# FE_Channel.net
KiCad netlist of a schematic drawn in Altium Designer
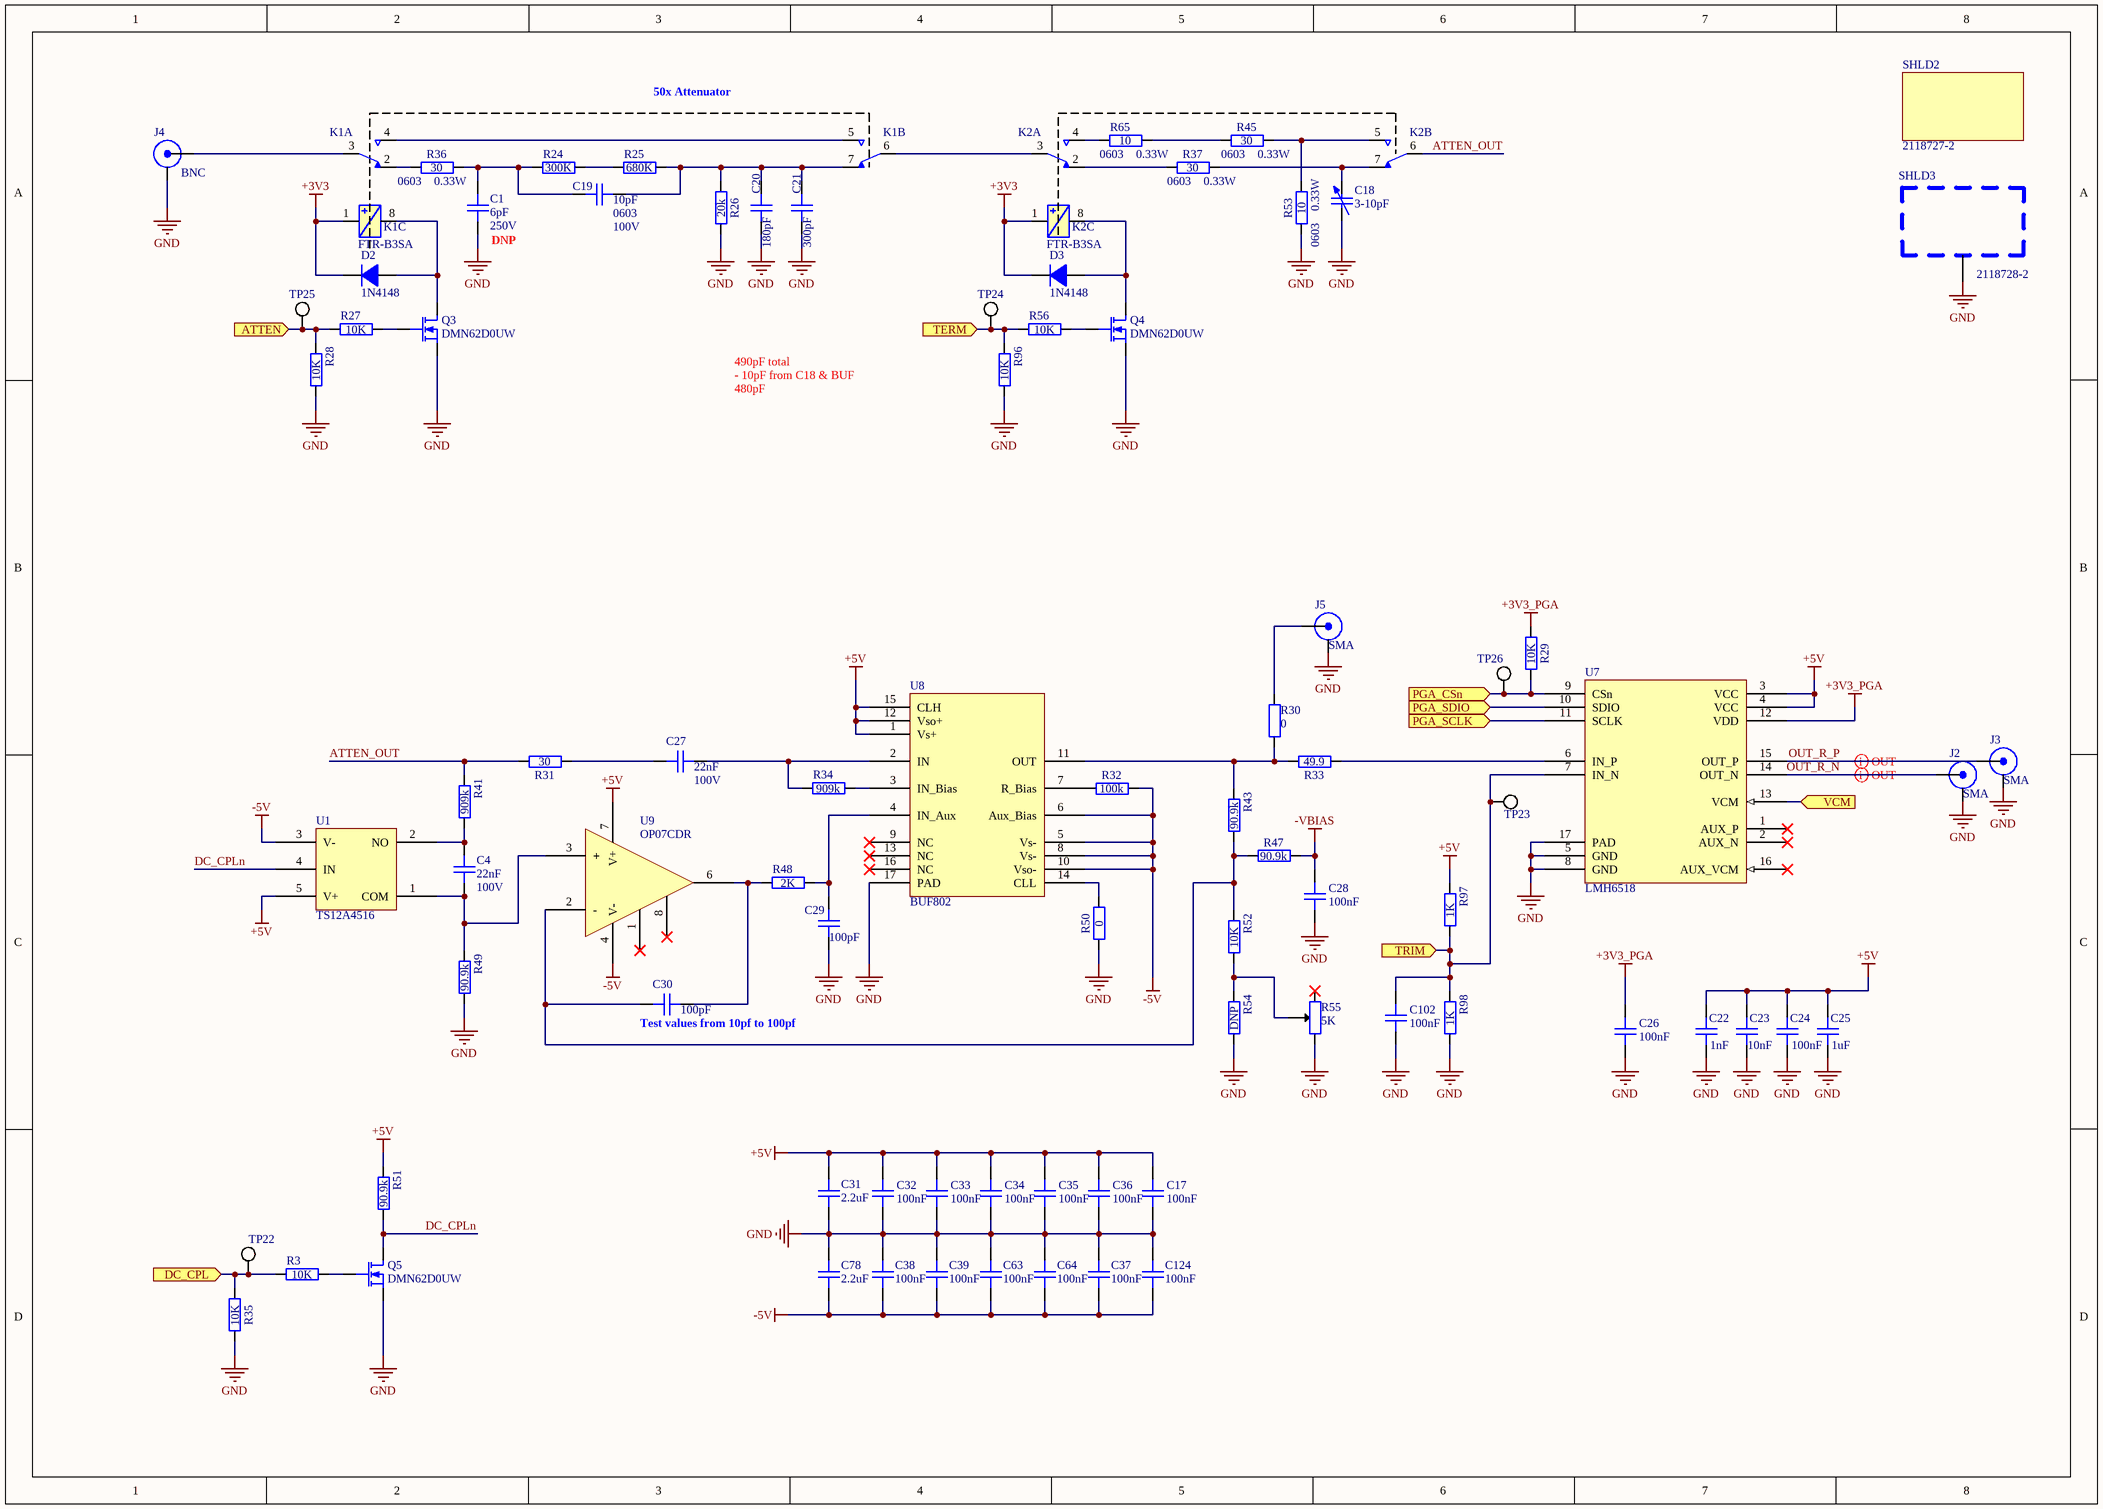
[diagram p0: FE_Channel.SchDoc]

(export (version "E")
  (design (tool "Eeschema 10.0.6"))
  (components
    (comp (ref "C1")
      (value "6pF")
      (footprint "GEN_C_0603")
      (fields
        (field (name "MANUFACTURER") "KEMET")
        (field (name "MANUFACTURER PART NUMBER") "CBR06C609BAGAC")
        (field (name "VOLTAGE RATING") "250V")
      )
      (libsource (lib "DSO") (part "CAP 6pF 250V C0G 0603"))
    )
    (comp (ref "C4")
      (value "22nF")
      (footprint "GEN_C_0603")
      (fields (field (name "VOLTAGE RATING") "100V"))
      (libsource (lib "DSO") (part "CAP 22nF 100V X7R 0603"))
    )
    (comp (ref "C17")
      (value "100nF")
      (footprint "GEN_C_0402")
      (libsource (lib "DSO") (part "CAP 100nF 16V X7R 0402"))
    )
    (comp (ref "C18")
      (value "3-10pF")
      (footprint "EW_TRIMCAP")
      (fields (field (name "MANUFACTURER") "Panasonic") (field (name "MANUFACTURER PART NUMBER") "SGC3S100"))
      (libsource (lib "DSO") (part "CAP TRIMMER 3-10PF 100V SMD"))
    )
    (comp (ref "C19")
      (value "10pF")
      (footprint "GEN_C_0603")
      (fields (field (name "PACKAGE") "0603") (field (name "VOLTAGE RATING") "100V"))
      (libsource (lib "DSO") (part "CAP 10pF 100V C0G 0603"))
    )
    (comp (ref "C20")
      (value "180pF")
      (footprint "GEN_C_0402")
      (fields
        (field (name "MANUFACTURER") "Murata")
        (field (name "MANUFACTURER PART NUMBER") "GCM1555C1H301FA16D")
      )
      (libsource (lib "DSO") (part "CAP 180pF 50V C0G 0402"))
    )
    (comp (ref "C21")
      (value "300pF")
      (footprint "GEN_C_0402")
      (libsource (lib "DSO") (part "CAP 300pF 50V C0G 0402"))
    )
    (comp (ref "C22")
      (value "1nF")
      (footprint "GEN_C_0402")
      (libsource (lib "DSO") (part "CAP 1nF 50V C0G 0402"))
    )
    (comp (ref "C23")
      (value "10nF")
      (footprint "GEN_C_0402")
      (libsource (lib "DSO") (part "CAP 10nF 50V X7R 0402"))
    )
    (comp (ref "C24")
      (value "100nF")
      (footprint "GEN_C_0402")
      (libsource (lib "DSO") (part "CAP 100nF 16V X7R 0402"))
    )
    (comp (ref "C25")
      (value "1uF")
      (footprint "GEN_C_0402")
      (libsource (lib "DSO") (part "CAP 1uF 25V X5R 0402"))
    )
    (comp (ref "C26")
      (value "100nF")
      (footprint "GEN_C_0402")
      (libsource (lib "DSO") (part "CAP 100nF 16V X7R 0402"))
    )
    (comp (ref "C27")
      (value "22nF")
      (footprint "GEN_C_0603")
      (fields (field (name "VOLTAGE RATING") "100V"))
      (libsource (lib "DSO") (part "CAP 22nF 100V X7R 0603"))
    )
    (comp (ref "C28")
      (value "100nF")
      (footprint "GEN_C_0402")
      (libsource (lib "DSO") (part "CAP 100nF 16V X7R 0402"))
    )
    (comp (ref "C29")
      (value "100pF")
      (footprint "GEN_C_0402")
      (libsource (lib "DSO") (part "CAP 100pF 50V C0G 0402"))
    )
    (comp (ref "C30")
      (value "100pF")
      (footprint "GEN_C_0402")
      (libsource (lib "DSO") (part "CAP 100pF 50V C0G 0402"))
    )
    (comp (ref "C31")
      (value "2.2uF")
      (footprint "GEN_C_0402")
      (libsource (lib "DSO") (part "CAP 2.2uF 10V X5R 0402"))
    )
    (comp (ref "C32")
      (value "100nF")
      (footprint "GEN_C_0402")
      (libsource (lib "DSO") (part "CAP 100nF 16V X7R 0402"))
    )
    (comp (ref "C33")
      (value "100nF")
      (footprint "GEN_C_0402")
      (libsource (lib "DSO") (part "CAP 100nF 16V X7R 0402"))
    )
    (comp (ref "C34")
      (value "100nF")
      (footprint "GEN_C_0402")
      (libsource (lib "DSO") (part "CAP 100nF 16V X7R 0402"))
    )
    (comp (ref "C35")
      (value "100nF")
      (footprint "GEN_C_0402")
      (libsource (lib "DSO") (part "CAP 100nF 16V X7R 0402"))
    )
    (comp (ref "C36")
      (value "100nF")
      (footprint "GEN_C_0402")
      (libsource (lib "DSO") (part "CAP 100nF 16V X7R 0402"))
    )
    (comp (ref "C37")
      (value "100nF")
      (footprint "GEN_C_0402")
      (libsource (lib "DSO") (part "CAP 100nF 16V X7R 0402"))
    )
    (comp (ref "C38")
      (value "100nF")
      (footprint "GEN_C_0402")
      (libsource (lib "DSO") (part "CAP 100nF 16V X7R 0402"))
    )
    (comp (ref "C39")
      (value "100nF")
      (footprint "GEN_C_0402")
      (libsource (lib "DSO") (part "CAP 100nF 16V X7R 0402"))
    )
    (comp (ref "C63")
      (value "100nF")
      (footprint "GEN_C_0402")
      (libsource (lib "DSO") (part "CAP 100nF 16V X7R 0402"))
    )
    (comp (ref "C64")
      (value "100nF")
      (footprint "GEN_C_0402")
      (libsource (lib "DSO") (part "CAP 100nF 16V X7R 0402"))
    )
    (comp (ref "C78")
      (value "2.2uF")
      (footprint "GEN_C_0402")
      (libsource (lib "DSO") (part "CAP 2.2uF 10V X5R 0402"))
    )
    (comp (ref "C102")
      (value "100nF")
      (footprint "GEN_C_0402")
      (libsource (lib "DSO") (part "CAP 100nF 16V X7R 0402"))
    )
    (comp (ref "C124")
      (value "100nF")
      (footprint "GEN_C_0402")
      (libsource (lib "DSO") (part "CAP 100nF 16V X7R 0402"))
    )
    (comp (ref "D2") (value "1N4148") (footprint "GEN_SOD_323") (libsource (lib "DSO") (part "DIODE 1N4148")))
    (comp (ref "D3") (value "1N4148") (footprint "GEN_SOD_323") (libsource (lib "DSO") (part "DIODE 1N4148")))
    (comp (ref "J2")
      (value "SMA")
      (footprint "MOL_0733910083")
      (fields (field (name "MANUFACTURER") "Molex") (field (name "MANUFACTURER PART NUMBER") "73100-0105"))
      (libsource (lib "DSO") (part "SMA JACK R/A"))
    )
    (comp (ref "J3")
      (value "SMA")
      (footprint "MOL_0733910083")
      (fields (field (name "MANUFACTURER") "Molex") (field (name "MANUFACTURER PART NUMBER") "73100-0105"))
      (libsource (lib "DSO") (part "SMA JACK R/A"))
    )
    (comp (ref "J4") (value "BNC") (footprint "MOL_0731000105") (libsource (lib "DSO") (part "BNC JACK R/A")))
    (comp (ref "J5")
      (value "SMA")
      (footprint "MOL_0733910083")
      (fields (field (name "MANUFACTURER") "Molex") (field (name "MANUFACTURER PART NUMBER") "73100-0105"))
      (libsource (lib "DSO") (part "SMA JACK R/A"))
    )
    (comp (ref "K1")
      (value "FTR-B3SA")
      (footprint "FUJ_FTR-B3SA")
      (libsource (lib "DSO") (part "RELAY DPDT-NO FTR-B3SA"))
    )
    (comp (ref "K2")
      (value "FTR-B3SA")
      (footprint "FUJ_FTR-B3SA")
      (libsource (lib "DSO") (part "RELAY DPDT-NO FTR-B3SA"))
    )
    (comp (ref "Q3")
      (value "DMN62D0UW")
      (footprint "GEN_SOT_323")
      (libsource (lib "DSO") (part "NMOS DMN62D0UW"))
    )
    (comp (ref "Q4")
      (value "DMN62D0UW")
      (footprint "GEN_SOT_323")
      (libsource (lib "DSO") (part "NMOS DMN62D0UW"))
    )
    (comp (ref "Q5")
      (value "DMN62D0UW")
      (footprint "GEN_SOT_323")
      (libsource (lib "DSO") (part "NMOS DMN62D0UW"))
    )
    (comp (ref "R3")
      (value "10K")
      (footprint "GEN_R_0402")
      (fields (field (name "TOLERANCE") "1%"))
      (libsource (lib "") (part "RES 10K OHM 1% 1/10W 0402_2"))
    )
    (comp (ref "R24")
      (value "300K")
      (footprint "GEN_R_0402")
      (fields
        (field (name "TOLERANCE") "1%")
        (field (name "MANUFACTURER") "Panasonic")
        (field (name "MANUFACTURER PART NUMBER") "ERJ-2RKF3003X")
      )
      (libsource (lib "DSO") (part "RES 300K OHM 1% 1/10W 0402"))
    )
    (comp (ref "R25")
      (value "680K")
      (footprint "GEN_R_0402")
      (fields
        (field (name "TOLERANCE") "1%")
        (field (name "MANUFACTURER") "Yageo")
        (field (name "MANUFACTURER PART NUMBER") "RC0402FR-07681KL")
      )
      (libsource (lib "DSO") (part "RES 680K OHM 1% 1/16W 0402"))
    )
    (comp (ref "R26")
      (value "20k")
      (footprint "GEN_R_0402")
      (fields
        (field (name "TOLERANCE") "1%")
        (field (name "MANUFACTURER") "Yageo")
        (field (name "MANUFACTURER PART NUMBER") "RC0402FR-0720KL")
      )
      (libsource (lib "DSO") (part "RES 20K OHM 1% 1/16W 0402"))
    )
    (comp (ref "R27")
      (value "10K")
      (footprint "GEN_R_0402")
      (fields (field (name "TOLERANCE") "1%"))
      (libsource (lib "") (part "RES 10K OHM 1% 1/10W 0402_2"))
    )
    (comp (ref "R28")
      (value "10K")
      (footprint "GEN_R_0402")
      (fields (field (name "TOLERANCE") "1%"))
      (libsource (lib "DSO") (part "RES 10K OHM 1% 1/10W 0402"))
    )
    (comp (ref "R29")
      (value "10K")
      (footprint "GEN_R_0402")
      (fields (field (name "TOLERANCE") "1%"))
      (libsource (lib "DSO") (part "RES 10K OHM 1% 1/10W 0402"))
    )
    (comp (ref "R30")
      (value "0")
      (footprint "GEN_R_0402")
      (fields
        (field (name "MANUFACTURER") "Yageo")
        (field (name "MANUFACTURER PART NUMBER") "RC0402JR-070RL")
      )
      (libsource (lib "DSO") (part "RES 0 OHM 1/16W 0402"))
    )
    (comp (ref "R31")
      (value "30")
      (footprint "GEN_R_0603")
      (fields
        (field (name "TOLERANCE") "1%")
        (field (name "MANUFACTURER") "KOA Speer")
        (field (name "MANUFACTURER PART NUMBER") "SG73P1JTTD30R0F")
      )
      (libsource (lib "DSO") (part "RES 30 OHM 1% 1/3W 0603"))
    )
    (comp (ref "R32")
      (value "100k")
      (footprint "GEN_R_0402")
      (fields (field (name "TOLERANCE") "1%"))
      (libsource (lib "DSO") (part "RES 100K OHM 1% 1/10W 0402"))
    )
    (comp (ref "R33")
      (value "49.9")
      (footprint "GEN_R_0402")
      (fields
        (field (name "TOLERANCE") "1%")
        (field (name "MANUFACTURER") "Yageo")
        (field (name "MANUFACTURER PART NUMBER") "RC0402FR-0749R9L")
      )
      (libsource (lib "DSO") (part "RES 49.9 OHM 1% 1/10W 0402"))
    )
    (comp (ref "R34")
      (value "909k")
      (footprint "GEN_R_0402")
      (fields (field (name "TOLERANCE") "1%"))
      (libsource (lib "") (part "RES 909K OHM 1% 1/16W 0402_1"))
    )
    (comp (ref "R35")
      (value "10K")
      (footprint "GEN_R_0402")
      (fields
        (field (name "TOLERANCE") "1%")
        (field (name "MANUFACTURER") "Panasonic")
        (field (name "MANUFACTURER PART NUMBER") "ERJ-2RKF1002X")
      )
      (libsource (lib "") (part "RES 10K OHM 1% 1/10W 0402_1"))
    )
    (comp (ref "R36")
      (value "30")
      (footprint "GEN_R_0603")
      (fields
        (field (name "TOLERANCE") "1%")
        (field (name "POWER RATING") "0.33W")
        (field (name "PACKAGE") "0603")
      )
      (libsource (lib "DSO") (part "RES 30 OHM 1% 1/3W 0603"))
    )
    (comp (ref "R37")
      (value "30")
      (footprint "GEN_R_0603")
      (fields
        (field (name "TOLERANCE") "1%")
        (field (name "POWER RATING") "0.33W")
        (field (name "PACKAGE") "0603")
      )
      (libsource (lib "DSO") (part "RES 30 OHM 1% 1/3W 0603"))
    )
    (comp (ref "R41")
      (value "909k")
      (footprint "GEN_R_0402")
      (fields (field (name "TOLERANCE") "1%"))
      (libsource (lib "DSO") (part "RES 909K OHM 1% 1/16W 0402"))
    )
    (comp (ref "R43")
      (value "90.9k")
      (footprint "GEN_R_0402")
      (fields (field (name "TOLERANCE") "1%"))
      (libsource (lib "") (part "RES 90.9K OHM 1% 1/16W 0402_1"))
    )
    (comp (ref "R45")
      (value "30")
      (footprint "GEN_R_0603")
      (fields
        (field (name "TOLERANCE") "1%")
        (field (name "POWER RATING") "0.33W")
        (field (name "PACKAGE") "0603")
      )
      (libsource (lib "DSO") (part "RES 30 OHM 1% 1/3W 0603"))
    )
    (comp (ref "R47")
      (value "90.9k")
      (footprint "GEN_R_0402")
      (fields (field (name "TOLERANCE") "1%"))
      (libsource (lib "DSO") (part "RES 90.9K OHM 1% 1/16W 0402"))
    )
    (comp (ref "R48")
      (value "2K")
      (footprint "GEN_R_0402")
      (fields (field (name "TOLERANCE") "1%"))
      (libsource (lib "DSO") (part "RES 2K OHM 1% 1/16W 0402"))
    )
    (comp (ref "R49")
      (value "90.9k")
      (footprint "GEN_R_0402")
      (fields (field (name "TOLERANCE") "1%"))
      (libsource (lib "") (part "RES 90.9K OHM 1% 1/16W 0402_1"))
    )
    (comp (ref "R50")
      (value "0")
      (footprint "GEN_R_0402")
      (libsource (lib "DSO") (part "RES 0 OHM 1/16W 0402"))
    )
    (comp (ref "R51")
      (value "90.9k")
      (footprint "GEN_R_0402")
      (fields (field (name "TOLERANCE") "1%"))
      (libsource (lib "") (part "RES 90.9K OHM 1% 1/16W 0402_1"))
    )
    (comp (ref "R52")
      (value "10K")
      (footprint "GEN_R_0402")
      (fields (field (name "TOLERANCE") "1%"))
      (libsource (lib "DSO") (part "RES 10K OHM 1% 1/10W 0402"))
    )
    (comp (ref "R53")
      (value "10")
      (footprint "GEN_R_0603")
      (fields
        (field (name "TOLERANCE") "1%")
        (field (name "POWER RATING") "0.33W")
        (field (name "PACKAGE") "0603")
      )
      (libsource (lib "") (part "RES 10 OHM 1% 1/3W 0603_1"))
    )
    (comp (ref "R54")
      (value "DNP")
      (footprint "GEN_R_0402")
      (fields (field (name "TOLERANCE") "1%"))
      (libsource (lib "DSO") (part "RES DNP 0402"))
    )
    (comp (ref "R55")
      (value "5K")
      (footprint "BOU_3mm_POT")
      (fields (field (name "TOLERANCE") "1%"))
      (libsource (lib "DSO") (part "TRIMMER 5K OHM 0.1W J LEAD TOP"))
    )
    (comp (ref "R56")
      (value "10K")
      (footprint "GEN_R_0402")
      (fields (field (name "TOLERANCE") "1%"))
      (libsource (lib "") (part "RES 10K OHM 1% 1/10W 0402_2"))
    )
    (comp (ref "R65")
      (value "10")
      (footprint "GEN_R_0603")
      (fields
        (field (name "PACKAGE") "0603")
        (field (name "TOLERANCE") "1%")
        (field (name "POWER RATING") "0.33W")
      )
      (libsource (lib "DSO") (part "RES 10 OHM 1% 1/3W 0603"))
    )
    (comp (ref "R96")
      (value "10K")
      (footprint "GEN_R_0402")
      (fields (field (name "TOLERANCE") "1%"))
      (libsource (lib "DSO") (part "RES 10K OHM 1% 1/10W 0402"))
    )
    (comp (ref "R97")
      (value "1K")
      (footprint "GEN_R_0402")
      (fields (field (name "TOLERANCE") "1%"))
      (libsource (lib "DSO") (part "RES 1K OHM 1% 1/10W 0402"))
    )
    (comp (ref "R98")
      (value "1K")
      (footprint "GEN_R_0402")
      (fields (field (name "TOLERANCE") "1%"))
      (libsource (lib "DSO") (part "RES 1K OHM 1% 1/10W 0402"))
    )
    (comp (ref "SHLD2") (value "2118727-2") (libsource (lib "DSO") (part "SHIELD 2118727-2")))
    (comp (ref "SHLD3")
      (value "2118728-2")
      (footprint "TE_2118728-2")
      (libsource (lib "DSO") (part "SHIELD 2118728-2"))
    )
    (comp (ref "TP22") (value "PCB") (footprint "GEN_TP_PCB") (libsource (lib "DSO") (part "TP PCB 1mm")))
    (comp (ref "TP23") (value "PCB") (footprint "GEN_TP_PCB") (libsource (lib "DSO") (part "TP PCB 1mm")))
    (comp (ref "TP24") (value "PCB") (footprint "GEN_TP_PCB") (libsource (lib "DSO") (part "TP PCB 1mm")))
    (comp (ref "TP25") (value "PCB") (footprint "GEN_TP_PCB") (libsource (lib "DSO") (part "TP PCB 1mm")))
    (comp (ref "TP26") (value "PCB") (footprint "GEN_TP_PCB") (libsource (lib "DSO") (part "TP PCB 1mm")))
    (comp (ref "U1")
      (value "TS12A4516")
      (footprint "GEN_SOT23_5_950_2900X1600X1450")
      (fields
        (field (name "MANUFACTURER") "Texas Instruments")
        (field (name "MANUFACTURER PART NUMBER") "TS12A4516DBVR")
      )
      (libsource (lib "DSO") (part "IC SWITCH SPST TS12A4516DBVR"))
    )
    (comp (ref "U7")
      (value "LMH6518")
      (footprint "TI_WQFN_RGH0016A")
      (libsource (lib "DSO") (part "IC PGA LMH6518"))
    )
    (comp (ref "U8")
      (value "BUF802")
      (footprint "TI_VQFN_RGT0016C")
      (libsource (lib "DSO") (part "IC BUFFER AMP BUF802"))
    )
    (comp (ref "U9")
      (value "OP07CDR")
      (footprint "TI_SOIC8_D0008A")
      (libsource (lib "DSO") (part "IC OPAMP OP07CDR"))
    )
  )
  (nets
    (net (code "1") (name "+3V3") (class "Default")
      (node (ref "D2") (pin "1") (pinfunction "K_1") (pintype "passive"))
      (node (ref "D3") (pin "1") (pinfunction "K_1") (pintype "passive"))
      (node (ref "K1") (pin "1") (pinfunction "1_1") (pintype "passive"))
      (node (ref "K2") (pin "1") (pinfunction "1_1") (pintype "passive"))
    )
    (net (code "2") (name "+3V3_PGA") (class "Default")
      (node (ref "C26") (pin "2") (pinfunction "2_2") (pintype "passive"))
      (node (ref "R29") (pin "2") (pinfunction "2_2") (pintype "passive"))
      (node (ref "U7") (pin "12") (pinfunction "VDD_12") (pintype "power_in"))
    )
    (net (code "3") (name "+5V") (class "Default")
      (node (ref "C17") (pin "2") (pinfunction "2_2") (pintype "passive"))
      (node (ref "C22") (pin "2") (pinfunction "2_2") (pintype "passive"))
      (node (ref "C23") (pin "2") (pinfunction "2_2") (pintype "passive"))
      (node (ref "C24") (pin "2") (pinfunction "2_2") (pintype "passive"))
      (node (ref "C25") (pin "2") (pinfunction "2_2") (pintype "passive"))
      (node (ref "C31") (pin "2") (pinfunction "2_2") (pintype "passive"))
      (node (ref "C32") (pin "1") (pinfunction "1_1") (pintype "passive"))
      (node (ref "C33") (pin "1") (pinfunction "1_1") (pintype "passive"))
      (node (ref "C34") (pin "1") (pinfunction "1_1") (pintype "passive"))
      (node (ref "C35") (pin "2") (pinfunction "2_2") (pintype "passive"))
      (node (ref "C36") (pin "2") (pinfunction "2_2") (pintype "passive"))
      (node (ref "R51") (pin "2") (pinfunction "2_2") (pintype "passive"))
      (node (ref "R97") (pin "2") (pinfunction "2_2") (pintype "passive"))
      (node (ref "U1") (pin "5") (pinfunction "V+_5") (pintype "passive"))
      (node (ref "U7") (pin "3") (pinfunction "VCC_3") (pintype "power_in"))
      (node (ref "U7") (pin "4") (pinfunction "VCC_4") (pintype "power_in"))
      (node (ref "U8") (pin "1") (pinfunction "Vs+_1") (pintype "passive"))
      (node (ref "U8") (pin "12") (pinfunction "Vso+_12") (pintype "passive"))
      (node (ref "U8") (pin "15") (pinfunction "CLH_15") (pintype "passive"))
      (node (ref "U9") (pin "7") (pinfunction "V+_7") (pintype "passive"))
    )
    (net (code "4") (name "-5V") (class "Default")
      (node (ref "C124") (pin "2") (pinfunction "2_2") (pintype "passive"))
      (node (ref "C37") (pin "2") (pinfunction "2_2") (pintype "passive"))
      (node (ref "C38") (pin "2") (pinfunction "2_2") (pintype "passive"))
      (node (ref "C39") (pin "1") (pinfunction "1_1") (pintype "passive"))
      (node (ref "C63") (pin "1") (pinfunction "1_1") (pintype "passive"))
      (node (ref "C64") (pin "1") (pinfunction "1_1") (pintype "passive"))
      (node (ref "C78") (pin "2") (pinfunction "2_2") (pintype "passive"))
      (node (ref "R32") (pin "2") (pinfunction "2_2") (pintype "passive"))
      (node (ref "U1") (pin "3") (pinfunction "V-_3") (pintype "passive"))
      (node (ref "U8") (pin "10") (pinfunction "Vso-_10") (pintype "passive"))
      (node (ref "U8") (pin "5") (pinfunction "Vs-_5") (pintype "passive"))
      (node (ref "U8") (pin "6") (pinfunction "Aux_Bias_6") (pintype "passive"))
      (node (ref "U8") (pin "8") (pinfunction "Vs-_8") (pintype "passive"))
      (node (ref "U9") (pin "4") (pinfunction "V-_4") (pintype "passive"))
    )
    (net (code "5") (name "-VBIAS") (class "Default")
      (node (ref "C28") (pin "1") (pinfunction "1_1") (pintype "passive"))
      (node (ref "R47") (pin "1") (pinfunction "1_1") (pintype "passive"))
    )
    (net (code "6") (name "/ATTEN") (class "Default")
      (node (ref "R27") (pin "2") (pinfunction "2_2") (pintype "passive"))
      (node (ref "R28") (pin "2") (pinfunction "2_2") (pintype "passive"))
      (node (ref "TP25") (pin "1") (pinfunction "1_1") (pintype "passive"))
    )
    (net (code "7") (name "/ATTEN_OUT") (class "Default")
      (node (ref "K2") (pin "6") (pinfunction "6_6") (pintype "passive"))
      (node (ref "R31") (pin "1") (pinfunction "1_1") (pintype "passive"))
      (node (ref "R41") (pin "2") (pinfunction "2_2") (pintype "passive"))
    )
    (net (code "8") (name "/DC_CPL") (class "Default")
      (node (ref "R3") (pin "2") (pinfunction "2_2") (pintype "passive"))
      (node (ref "R35") (pin "2") (pinfunction "2_2") (pintype "passive"))
      (node (ref "TP22") (pin "1") (pinfunction "1_1") (pintype "passive"))
    )
    (net (code "9") (name "/DC_CPLn") (class "Default")
      (node (ref "Q5") (pin "1") (pinfunction "D_1") (pintype "passive"))
      (node (ref "R51") (pin "1") (pinfunction "1_1") (pintype "passive"))
      (node (ref "U1") (pin "4") (pinfunction "IN_4") (pintype "passive"))
    )
    (net (code "10") (name "/OUT_R_N") (class "Default")
      (node (ref "J2") (pin "1") (pinfunction "Signal_1") (pintype "passive"))
      (node (ref "U7") (pin "14") (pinfunction "OUT_N_14") (pintype "passive"))
    )
    (net (code "11") (name "/OUT_R_P") (class "Default")
      (node (ref "J3") (pin "1") (pinfunction "Signal_1") (pintype "passive"))
      (node (ref "U7") (pin "15") (pinfunction "OUT_P_15") (pintype "passive"))
    )
    (net (code "12") (name "/PGA_CSn") (class "Default")
      (node (ref "R29") (pin "1") (pinfunction "1_1") (pintype "passive"))
      (node (ref "TP26") (pin "1") (pinfunction "1_1") (pintype "passive"))
      (node (ref "U7") (pin "9") (pinfunction "CSn_9") (pintype "passive"))
    )
    (net (code "13") (name "/PGA_SCLK") (class "Default")
      (node (ref "U7") (pin "11") (pinfunction "SCLK_11") (pintype "passive"))
    )
    (net (code "14") (name "/PGA_SDIO") (class "Default")
      (node (ref "U7") (pin "10") (pinfunction "SDIO_10") (pintype "passive"))
    )
    (net (code "15") (name "/TERM") (class "Default")
      (node (ref "R56") (pin "2") (pinfunction "2_2") (pintype "passive"))
      (node (ref "R96") (pin "2") (pinfunction "2_2") (pintype "passive"))
      (node (ref "TP24") (pin "1") (pinfunction "1_1") (pintype "passive"))
    )
    (net (code "16") (name "/TRIM") (class "Default")
      (node (ref "C102") (pin "1") (pinfunction "1_1") (pintype "passive"))
      (node (ref "R97") (pin "1") (pinfunction "1_1") (pintype "passive"))
      (node (ref "R98") (pin "2") (pinfunction "2_2") (pintype "passive"))
      (node (ref "TP23") (pin "1") (pinfunction "1_1") (pintype "passive"))
      (node (ref "U7") (pin "7") (pinfunction "IN_N_7") (pintype "passive"))
    )
    (net (code "17") (name "/VCM") (class "Default")
      (node (ref "U7") (pin "13") (pinfunction "VCM_13") (pintype "input"))
    )
    (net (code "18") (name "GND") (class "Default")
      (node (ref "C1") (pin "1") (pinfunction "1_1") (pintype "passive"))
      (node (ref "C102") (pin "2") (pinfunction "2_2") (pintype "passive"))
      (node (ref "C124") (pin "1") (pinfunction "1_1") (pintype "passive"))
      (node (ref "C17") (pin "1") (pinfunction "1_1") (pintype "passive"))
      (node (ref "C18") (pin "2") (pinfunction "2_2") (pintype "passive"))
      (node (ref "C20") (pin "1") (pinfunction "1_1") (pintype "passive"))
      (node (ref "C21") (pin "1") (pinfunction "1_1") (pintype "passive"))
      (node (ref "C22") (pin "1") (pinfunction "1_1") (pintype "passive"))
      (node (ref "C23") (pin "1") (pinfunction "1_1") (pintype "passive"))
      (node (ref "C24") (pin "1") (pinfunction "1_1") (pintype "passive"))
      (node (ref "C25") (pin "1") (pinfunction "1_1") (pintype "passive"))
      (node (ref "C26") (pin "1") (pinfunction "1_1") (pintype "passive"))
      (node (ref "C28") (pin "2") (pinfunction "2_2") (pintype "passive"))
      (node (ref "C29") (pin "1") (pinfunction "1_1") (pintype "passive"))
      (node (ref "C31") (pin "1") (pinfunction "1_1") (pintype "passive"))
      (node (ref "C32") (pin "2") (pinfunction "2_2") (pintype "passive"))
      (node (ref "C33") (pin "2") (pinfunction "2_2") (pintype "passive"))
      (node (ref "C34") (pin "2") (pinfunction "2_2") (pintype "passive"))
      (node (ref "C35") (pin "1") (pinfunction "1_1") (pintype "passive"))
      (node (ref "C36") (pin "1") (pinfunction "1_1") (pintype "passive"))
      (node (ref "C37") (pin "1") (pinfunction "1_1") (pintype "passive"))
      (node (ref "C38") (pin "1") (pinfunction "1_1") (pintype "passive"))
      (node (ref "C39") (pin "2") (pinfunction "2_2") (pintype "passive"))
      (node (ref "C63") (pin "2") (pinfunction "2_2") (pintype "passive"))
      (node (ref "C64") (pin "2") (pinfunction "2_2") (pintype "passive"))
      (node (ref "C78") (pin "1") (pinfunction "1_1") (pintype "passive"))
      (node (ref "J2") (pin "2") (pinfunction "SHIELD_2") (pintype "passive"))
      (node (ref "J3") (pin "2") (pinfunction "SHIELD_2") (pintype "passive"))
      (node (ref "J4") (pin "2") (pinfunction "SHIELD_2") (pintype "passive"))
      (node (ref "J5") (pin "2") (pinfunction "SHIELD_2") (pintype "passive"))
      (node (ref "Q3") (pin "3") (pinfunction "S_3") (pintype "passive"))
      (node (ref "Q4") (pin "3") (pinfunction "S_3") (pintype "passive"))
      (node (ref "Q5") (pin "3") (pinfunction "S_3") (pintype "passive"))
      (node (ref "R26") (pin "1") (pinfunction "1_1") (pintype "passive"))
      (node (ref "R28") (pin "1") (pinfunction "1_1") (pintype "passive"))
      (node (ref "R35") (pin "1") (pinfunction "1_1") (pintype "passive"))
      (node (ref "R49") (pin "1") (pinfunction "1_1") (pintype "passive"))
      (node (ref "R50") (pin "1") (pinfunction "1_1") (pintype "passive"))
      (node (ref "R53") (pin "1") (pinfunction "1_1") (pintype "passive"))
      (node (ref "R54") (pin "1") (pinfunction "1_1") (pintype "passive"))
      (node (ref "R55") (pin "3") (pinfunction "3_3") (pintype "passive"))
      (node (ref "R96") (pin "1") (pinfunction "1_1") (pintype "passive"))
      (node (ref "R98") (pin "1") (pinfunction "1_1") (pintype "passive"))
      (node (ref "SHLD3") (pin "1") (pinfunction "1_1") (pintype "passive"))
      (node (ref "U7") (pin "17") (pinfunction "PAD_17") (pintype "power_in"))
      (node (ref "U7") (pin "5") (pinfunction "GND_5") (pintype "power_in"))
      (node (ref "U7") (pin "8") (pinfunction "GND_8") (pintype "power_in"))
      (node (ref "U8") (pin "17") (pinfunction "PAD_17") (pintype "passive"))
    )
    (net (code "19") (name "Net-(C1-Pad2)") (class "Default")
      (node (ref "C1") (pin "2") (pinfunction "2_2") (pintype "passive"))
      (node (ref "C19") (pin "2") (pinfunction "2_2") (pintype "passive"))
      (node (ref "R24") (pin "1") (pinfunction "1_1") (pintype "passive"))
      (node (ref "R36") (pin "2") (pinfunction "2_2") (pintype "passive"))
    )
    (net (code "20") (name "Net-(C18-Pad1)") (class "Default")
      (node (ref "C18") (pin "1") (pinfunction "1_1") (pintype "passive"))
      (node (ref "K2") (pin "7") (pinfunction "7_7") (pintype "passive"))
      (node (ref "R37") (pin "2") (pinfunction "2_2") (pintype "passive"))
    )
    (net (code "21") (name "Net-(C19-Pad1)") (class "Default")
      (node (ref "C19") (pin "1") (pinfunction "1_1") (pintype "passive"))
      (node (ref "C20") (pin "2") (pinfunction "2_2") (pintype "passive"))
      (node (ref "C21") (pin "2") (pinfunction "2_2") (pintype "passive"))
      (node (ref "K1") (pin "7") (pinfunction "7_7") (pintype "passive"))
      (node (ref "R25") (pin "2") (pinfunction "2_2") (pintype "passive"))
      (node (ref "R26") (pin "2") (pinfunction "2_2") (pintype "passive"))
    )
    (net (code "22") (name "Net-(C27-Pad2)") (class "Default")
      (node (ref "C27") (pin "2") (pinfunction "2_2") (pintype "passive"))
      (node (ref "R31") (pin "2") (pinfunction "2_2") (pintype "passive"))
    )
    (net (code "23") (name "Net-(D2-A)") (class "Default")
      (node (ref "D2") (pin "2") (pinfunction "A_2") (pintype "passive"))
      (node (ref "K1") (pin "8") (pinfunction "8_8") (pintype "passive"))
      (node (ref "Q3") (pin "1") (pinfunction "D_1") (pintype "passive"))
    )
    (net (code "24") (name "Net-(D3-A)") (class "Default")
      (node (ref "D3") (pin "2") (pinfunction "A_2") (pintype "passive"))
      (node (ref "K2") (pin "8") (pinfunction "8_8") (pintype "passive"))
      (node (ref "Q4") (pin "1") (pinfunction "D_1") (pintype "passive"))
    )
    (net (code "25") (name "Net-(J4-Signal)") (class "Default")
      (node (ref "J4") (pin "1") (pinfunction "Signal_1") (pintype "passive"))
      (node (ref "K1") (pin "3") (pinfunction "3_3") (pintype "passive"))
    )
    (net (code "26") (name "Net-(J5-Signal)") (class "Default")
      (node (ref "J5") (pin "1") (pinfunction "Signal_1") (pintype "passive"))
      (node (ref "R30") (pin "2") (pinfunction "2_2") (pintype "passive"))
    )
    (net (code "27") (name "Net-(K1-Pad2)") (class "Default")
      (node (ref "K1") (pin "2") (pinfunction "2_2") (pintype "passive"))
      (node (ref "R36") (pin "1") (pinfunction "1_1") (pintype "passive"))
    )
    (net (code "28") (name "Net-(K1-Pad4)") (class "Default")
      (node (ref "K1") (pin "4") (pinfunction "4_4") (pintype "passive"))
      (node (ref "K1") (pin "5") (pinfunction "5_5") (pintype "passive"))
    )
    (net (code "29") (name "Net-(K1-Pad6)") (class "Default")
      (node (ref "K1") (pin "6") (pinfunction "6_6") (pintype "passive"))
      (node (ref "K2") (pin "3") (pinfunction "3_3") (pintype "passive"))
    )
    (net (code "30") (name "Net-(K2-Pad2)") (class "Default")
      (node (ref "K2") (pin "2") (pinfunction "2_2") (pintype "passive"))
      (node (ref "R37") (pin "1") (pinfunction "1_1") (pintype "passive"))
    )
    (net (code "31") (name "Net-(K2-Pad4)") (class "Default")
      (node (ref "K2") (pin "4") (pinfunction "4_4") (pintype "passive"))
      (node (ref "R65") (pin "1") (pinfunction "1_1") (pintype "passive"))
    )
    (net (code "32") (name "Net-(K2-Pad5)") (class "Default")
      (node (ref "K2") (pin "5") (pinfunction "5_5") (pintype "passive"))
      (node (ref "R45") (pin "2") (pinfunction "2_2") (pintype "passive"))
      (node (ref "R53") (pin "2") (pinfunction "2_2") (pintype "passive"))
    )
    (net (code "33") (name "Net-(Q3-G)") (class "Default")
      (node (ref "Q3") (pin "2") (pinfunction "G_2") (pintype "passive"))
      (node (ref "R27") (pin "1") (pinfunction "1_1") (pintype "passive"))
    )
    (net (code "34") (name "Net-(Q4-G)") (class "Default")
      (node (ref "Q4") (pin "2") (pinfunction "G_2") (pintype "passive"))
      (node (ref "R56") (pin "1") (pinfunction "1_1") (pintype "passive"))
    )
    (net (code "35") (name "Net-(Q5-G)") (class "Default")
      (node (ref "Q5") (pin "2") (pinfunction "G_2") (pintype "passive"))
      (node (ref "R3") (pin "1") (pinfunction "1_1") (pintype "passive"))
    )
    (net (code "36") (name "Net-(R24-Pad2)") (class "Default")
      (node (ref "R24") (pin "2") (pinfunction "2_2") (pintype "passive"))
      (node (ref "R25") (pin "1") (pinfunction "1_1") (pintype "passive"))
    )
    (net (code "37") (name "Net-(R45-Pad1)") (class "Default")
      (node (ref "R45") (pin "1") (pinfunction "1_1") (pintype "passive"))
      (node (ref "R65") (pin "2") (pinfunction "2_2") (pintype "passive"))
    )
    (net (code "38") (name "Net-(R52-Pad1)") (class "Default")
      (node (ref "R52") (pin "1") (pinfunction "1_1") (pintype "passive"))
      (node (ref "R54") (pin "2") (pinfunction "2_2") (pintype "passive"))
      (node (ref "R55") (pin "2") (pinfunction "2_2") (pintype "passive"))
    )
    (net (code "39") (name "Net-(U1-COM)") (class "Default")
      (node (ref "C4") (pin "2") (pinfunction "2_2") (pintype "passive"))
      (node (ref "R49") (pin "2") (pinfunction "2_2") (pintype "passive"))
      (node (ref "U1") (pin "1") (pinfunction "COM_1") (pintype "passive"))
      (node (ref "U9") (pin "3") (pinfunction "+_3") (pintype "passive"))
    )
    (net (code "40") (name "Net-(U1-NO)") (class "Default")
      (node (ref "C4") (pin "1") (pinfunction "1_1") (pintype "passive"))
      (node (ref "R41") (pin "1") (pinfunction "1_1") (pintype "passive"))
      (node (ref "U1") (pin "2") (pinfunction "NO_2") (pintype "passive"))
    )
    (net (code "41") (name "Net-(U7-IN_P)") (class "Default")
      (node (ref "R33") (pin "2") (pinfunction "2_2") (pintype "passive"))
      (node (ref "U7") (pin "6") (pinfunction "IN_P_6") (pintype "passive"))
    )
    (net (code "42") (name "Net-(U8-CLL)") (class "Default")
      (node (ref "R50") (pin "2") (pinfunction "2_2") (pintype "passive"))
      (node (ref "U8") (pin "14") (pinfunction "CLL_14") (pintype "passive"))
    )
    (net (code "43") (name "Net-(U8-IN)") (class "Default")
      (node (ref "C27") (pin "1") (pinfunction "1_1") (pintype "passive"))
      (node (ref "R34") (pin "2") (pinfunction "2_2") (pintype "passive"))
      (node (ref "U8") (pin "2") (pinfunction "IN_2") (pintype "passive"))
    )
    (net (code "44") (name "Net-(U8-IN_Aux)") (class "Default")
      (node (ref "C29") (pin "2") (pinfunction "2_2") (pintype "passive"))
      (node (ref "R48") (pin "1") (pinfunction "1_1") (pintype "passive"))
      (node (ref "U8") (pin "4") (pinfunction "IN_Aux_4") (pintype "passive"))
    )
    (net (code "45") (name "Net-(U8-IN_Bias)") (class "Default")
      (node (ref "R34") (pin "1") (pinfunction "1_1") (pintype "passive"))
      (node (ref "U8") (pin "3") (pinfunction "IN_Bias_3") (pintype "passive"))
    )
    (net (code "46") (name "Net-(U8-OUT)") (class "Default")
      (node (ref "R30") (pin "1") (pinfunction "1_1") (pintype "passive"))
      (node (ref "R33") (pin "1") (pinfunction "1_1") (pintype "passive"))
      (node (ref "R43") (pin "2") (pinfunction "2_2") (pintype "passive"))
      (node (ref "U8") (pin "11") (pinfunction "OUT_11") (pintype "passive"))
    )
    (net (code "47") (name "Net-(U8-R_Bias)") (class "Default")
      (node (ref "R32") (pin "1") (pinfunction "1_1") (pintype "passive"))
      (node (ref "U8") (pin "7") (pinfunction "R_Bias_7") (pintype "passive"))
    )
    (net (code "48") (name "Net-(U9--)") (class "Default")
      (node (ref "C30") (pin "2") (pinfunction "2_2") (pintype "passive"))
      (node (ref "R43") (pin "1") (pinfunction "1_1") (pintype "passive"))
      (node (ref "R47") (pin "2") (pinfunction "2_2") (pintype "passive"))
      (node (ref "R52") (pin "2") (pinfunction "2_2") (pintype "passive"))
      (node (ref "U9") (pin "2") (pinfunction "-_2") (pintype "passive"))
    )
    (net (code "49") (name "Net-(U9-OUT)") (class "Default")
      (node (ref "C30") (pin "1") (pinfunction "1_1") (pintype "passive"))
      (node (ref "R48") (pin "2") (pinfunction "2_2") (pintype "passive"))
      (node (ref "U9") (pin "6") (pinfunction "OUT_6") (pintype "passive"))
    )
    (net (code "50") (name "unconnected-(R55-Pad1)") (class "Default")
      (node (ref "R55") (pin "1") (pinfunction "1_1") (pintype "passive+no_connect"))
    )
    (net (code "51") (name "unconnected-(U7-AUX_N-Pad2)") (class "Default")
      (node (ref "U7") (pin "2") (pinfunction "AUX_N_2") (pintype "passive+no_connect"))
    )
    (net (code "52") (name "unconnected-(U7-AUX_P-Pad1)") (class "Default")
      (node (ref "U7") (pin "1") (pinfunction "AUX_P_1") (pintype "passive+no_connect"))
    )
    (net (code "53") (name "unconnected-(U7-AUX_VCM-Pad16)") (class "Default")
      (node (ref "U7") (pin "16") (pinfunction "AUX_VCM_16") (pintype "input+no_connect"))
    )
    (net (code "54") (name "unconnected-(U8-NC-Pad9)") (class "Default")
      (node (ref "U8") (pin "9") (pinfunction "NC_9") (pintype "passive+no_connect"))
    )
    (net (code "55") (name "unconnected-(U8-NC-Pad13)") (class "Default")
      (node (ref "U8") (pin "13") (pinfunction "NC_13") (pintype "passive+no_connect"))
    )
    (net (code "56") (name "unconnected-(U8-NC-Pad16)") (class "Default")
      (node (ref "U8") (pin "16") (pinfunction "NC_16") (pintype "passive+no_connect"))
    )
    (net (code "57") (name "unconnected-(U9-N1-Pad1)") (class "Default")
      (node (ref "U9") (pin "1") (pinfunction "N1_1") (pintype "passive+no_connect"))
    )
    (net (code "58") (name "unconnected-(U9-N2-Pad8)") (class "Default")
      (node (ref "U9") (pin "8") (pinfunction "N2_8") (pintype "passive+no_connect"))
    )
  )
)
